# SCH_hacker-card_2024-07-15.net
KiCad netlist of a schematic drawn in EasyEDA
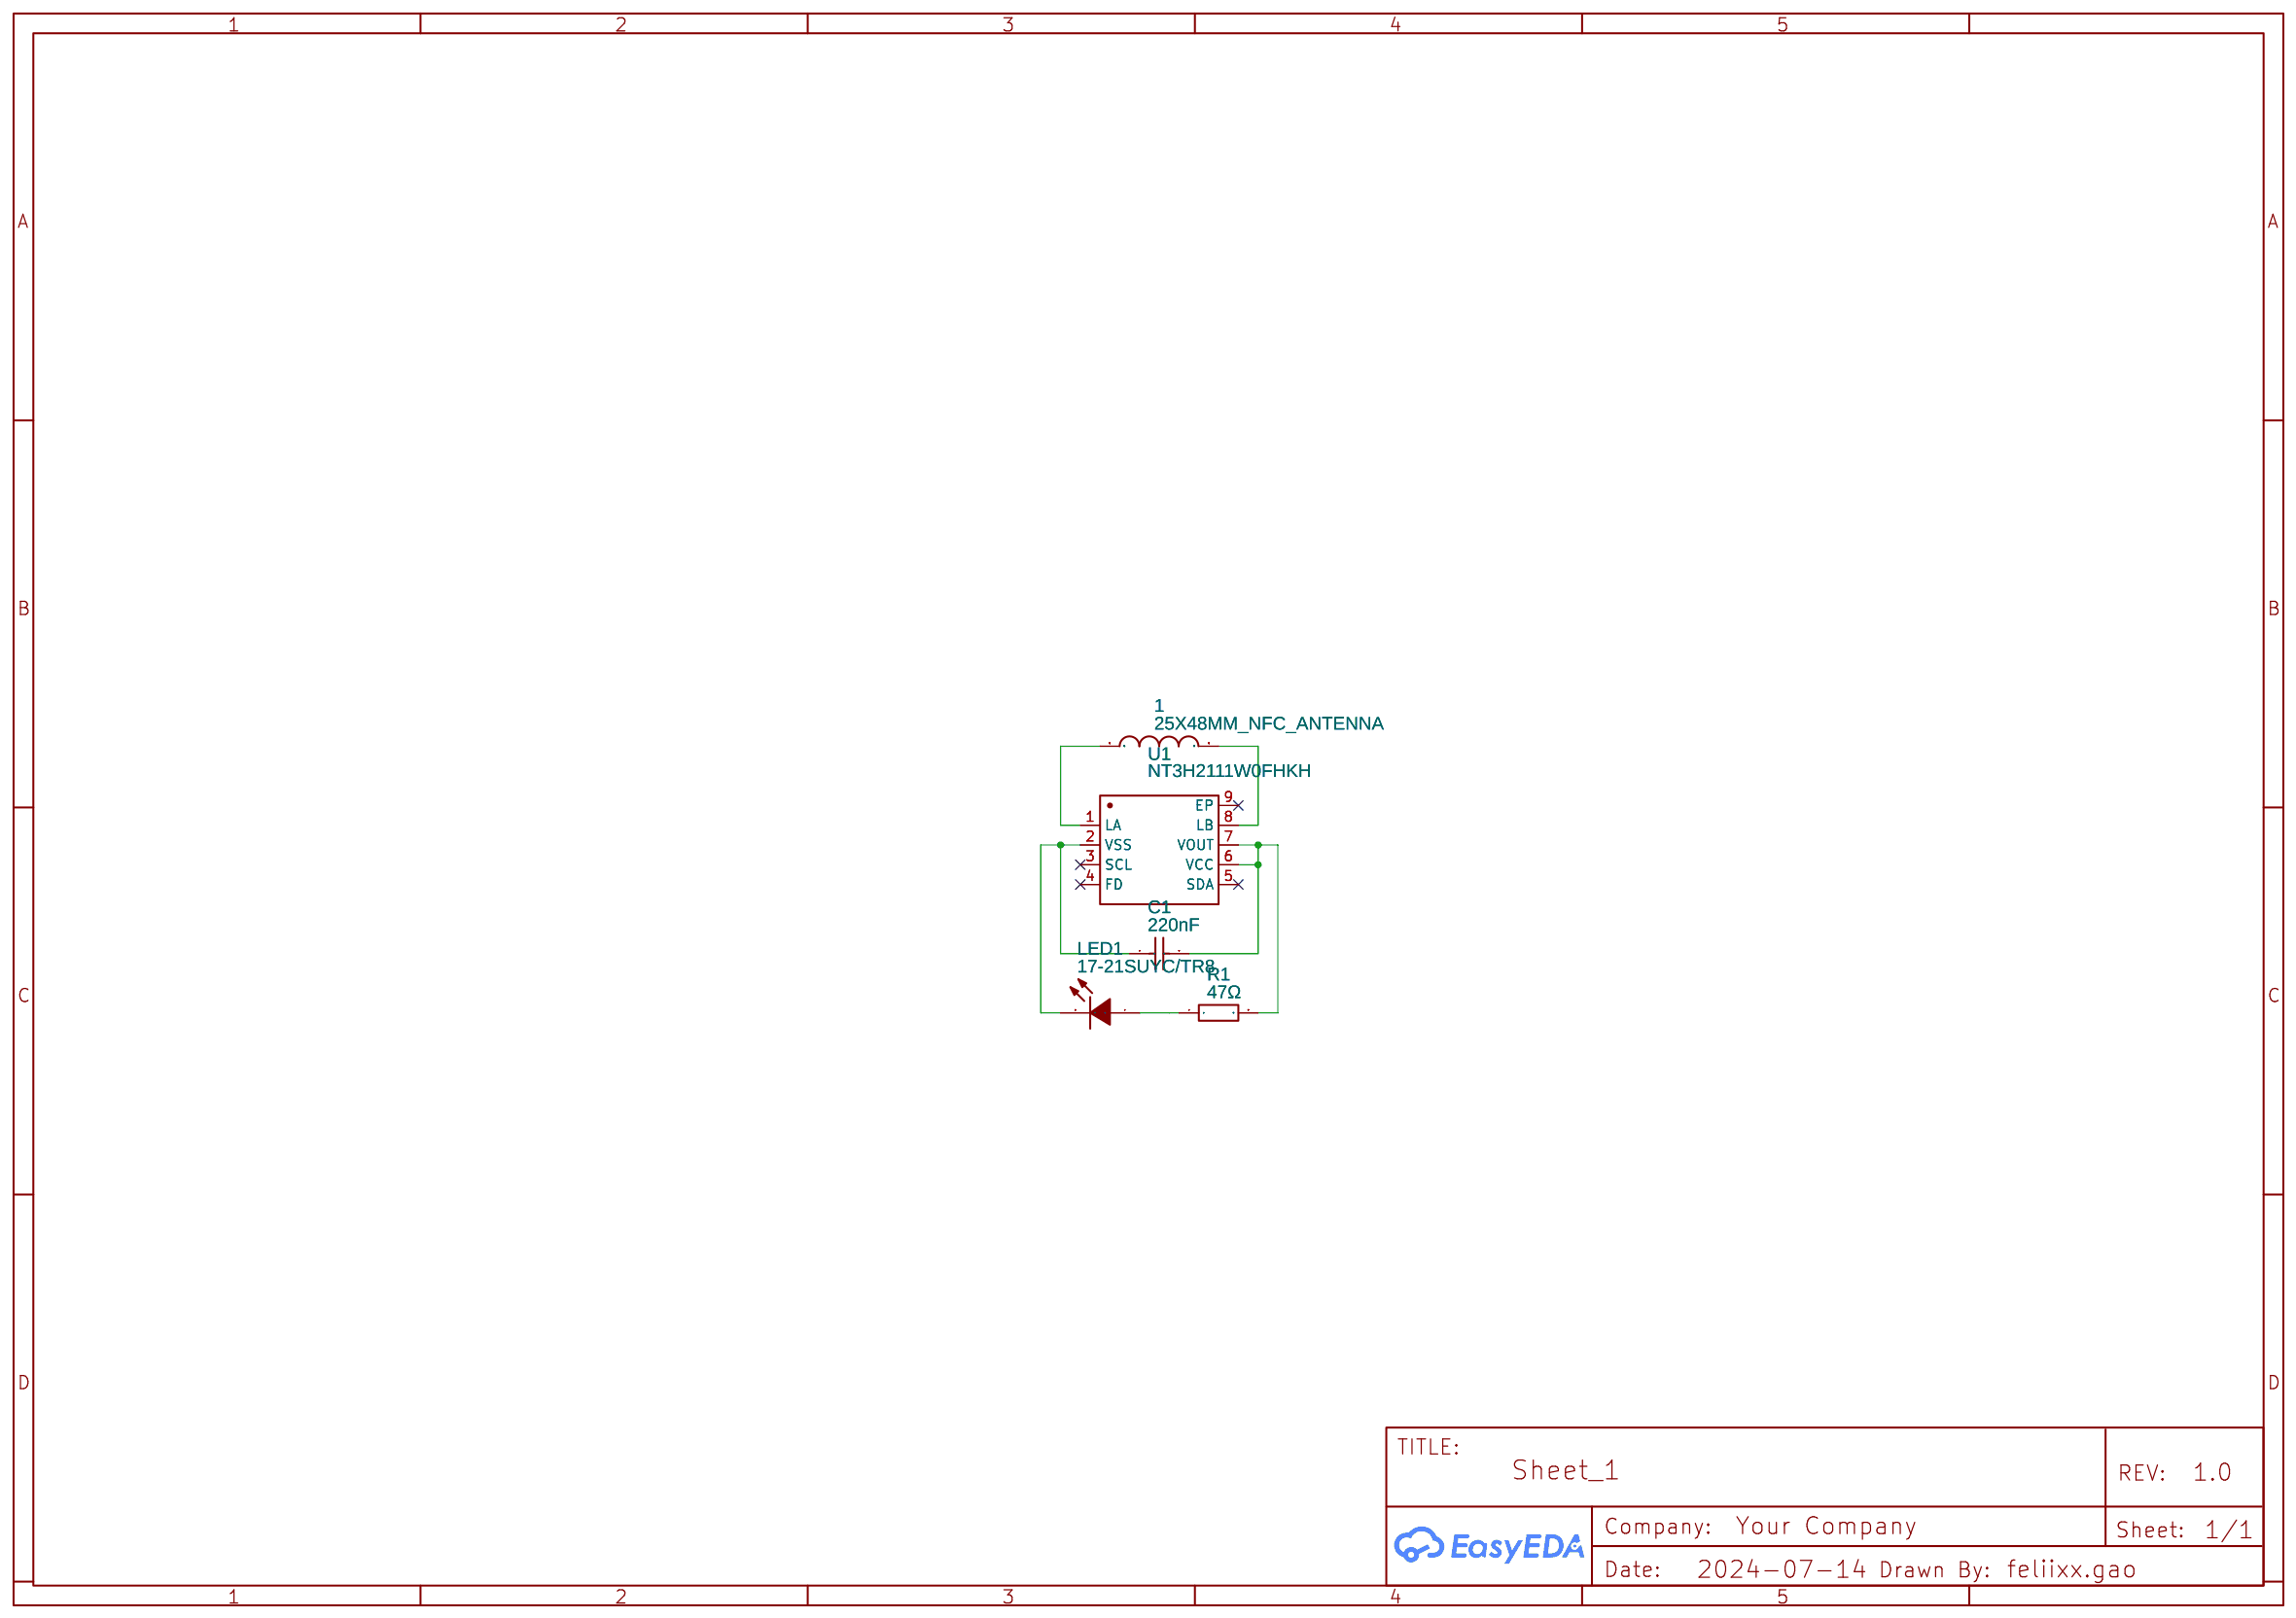
[diagram p0: schematic sheet]

(export (version "E")
  (design (tool "Eeschema 10.0.6"))
  (components
    (comp (ref "1") (value "25X48MM_NFC_ANTENNA") (libsource (lib "") (part "25X48MM_NFC_ANTENNA")))
    (comp (ref "C1")
      (value "220nF")
      (fields
        (field (name "Manufacturer Part") "CL10B224KA8NNNC")
        (field (name "Manufacturer") "SAMSUNG(三星)")
      )
      (libsource (lib "") (part "CL10B224KA8NNNC"))
    )
    (comp (ref "LED1")
      (value "17-21SUYC/TR8")
      (fields (field (name "Manufacturer Part") "KT-0805黄灯") (field (name "Manufacturer") "KENTO"))
      (libsource (lib "") (part "17-21SUYC/TR8"))
    )
    (comp (ref "R1")
      (value "47Ω")
      (fields
        (field (name "Manufacturer Part") "0603WAF470JT5E")
        (field (name "Manufacturer") "UNI-ROYAL(厚声)")
      )
      (libsource (lib "") (part "0603WAF470JT5E"))
    )
    (comp (ref "U1")
      (value "NT3H2111W0FHKH")
      (fields (field (name "Manufacturer") "NXP(恩智浦)"))
      (libsource (lib "") (part "NT3H2111W0FHKH"))
    )
  )
  (nets
    (net (code "1") (name "Net-(LED1-+)") (class "Default")
      (node (ref "LED1") (pin "1") (pinfunction "+_1") (pintype "unspecified"))
      (node (ref "R1") (pin "1") (pinfunction "1_1") (pintype "input"))
    )
    (net (code "2") (name "Net-(LED1--)") (class "Default")
      (node (ref "C1") (pin "1") (pinfunction "1_1") (pintype "input"))
      (node (ref "LED1") (pin "2") (pinfunction "-_2") (pintype "unspecified"))
      (node (ref "U1") (pin "2") (pinfunction "VSS_2") (pintype "unspecified"))
    )
    (net (code "3") (name "Net-(U1-LA)") (class "Default")
      (node (ref "1") (pin "P$1") (pinfunction "P$1_P$1") (pintype "bidirectional"))
      (node (ref "U1") (pin "1") (pinfunction "LA_1") (pintype "unspecified"))
    )
    (net (code "4") (name "Net-(U1-LB)") (class "Default")
      (node (ref "1") (pin "P$2") (pinfunction "P$2_P$2") (pintype "bidirectional"))
      (node (ref "U1") (pin "8") (pinfunction "LB_8") (pintype "unspecified"))
    )
    (net (code "5") (name "Net-(U1-VCC)") (class "Default")
      (node (ref "C1") (pin "2") (pinfunction "2_2") (pintype "input"))
      (node (ref "R1") (pin "2") (pinfunction "2_2") (pintype "input"))
      (node (ref "U1") (pin "6") (pinfunction "VCC_6") (pintype "unspecified"))
      (node (ref "U1") (pin "7") (pinfunction "VOUT_7") (pintype "unspecified"))
    )
    (net (code "6") (name "unconnected-(U1-EP-Pad9)") (class "Default")
      (node (ref "U1") (pin "9") (pinfunction "EP_9") (pintype "unspecified+no_connect"))
    )
    (net (code "7") (name "unconnected-(U1-FD-Pad4)") (class "Default")
      (node (ref "U1") (pin "4") (pinfunction "FD_4") (pintype "unspecified+no_connect"))
    )
    (net (code "8") (name "unconnected-(U1-SCL-Pad3)") (class "Default")
      (node (ref "U1") (pin "3") (pinfunction "SCL_3") (pintype "unspecified+no_connect"))
    )
    (net (code "9") (name "unconnected-(U1-SDA-Pad5)") (class "Default")
      (node (ref "U1") (pin "5") (pinfunction "SDA_5") (pintype "unspecified+no_connect"))
    )
  )
)
